# ArduTX_TX_Battery_Powered.net
KiCad netlist of a schematic drawn in EAGLE
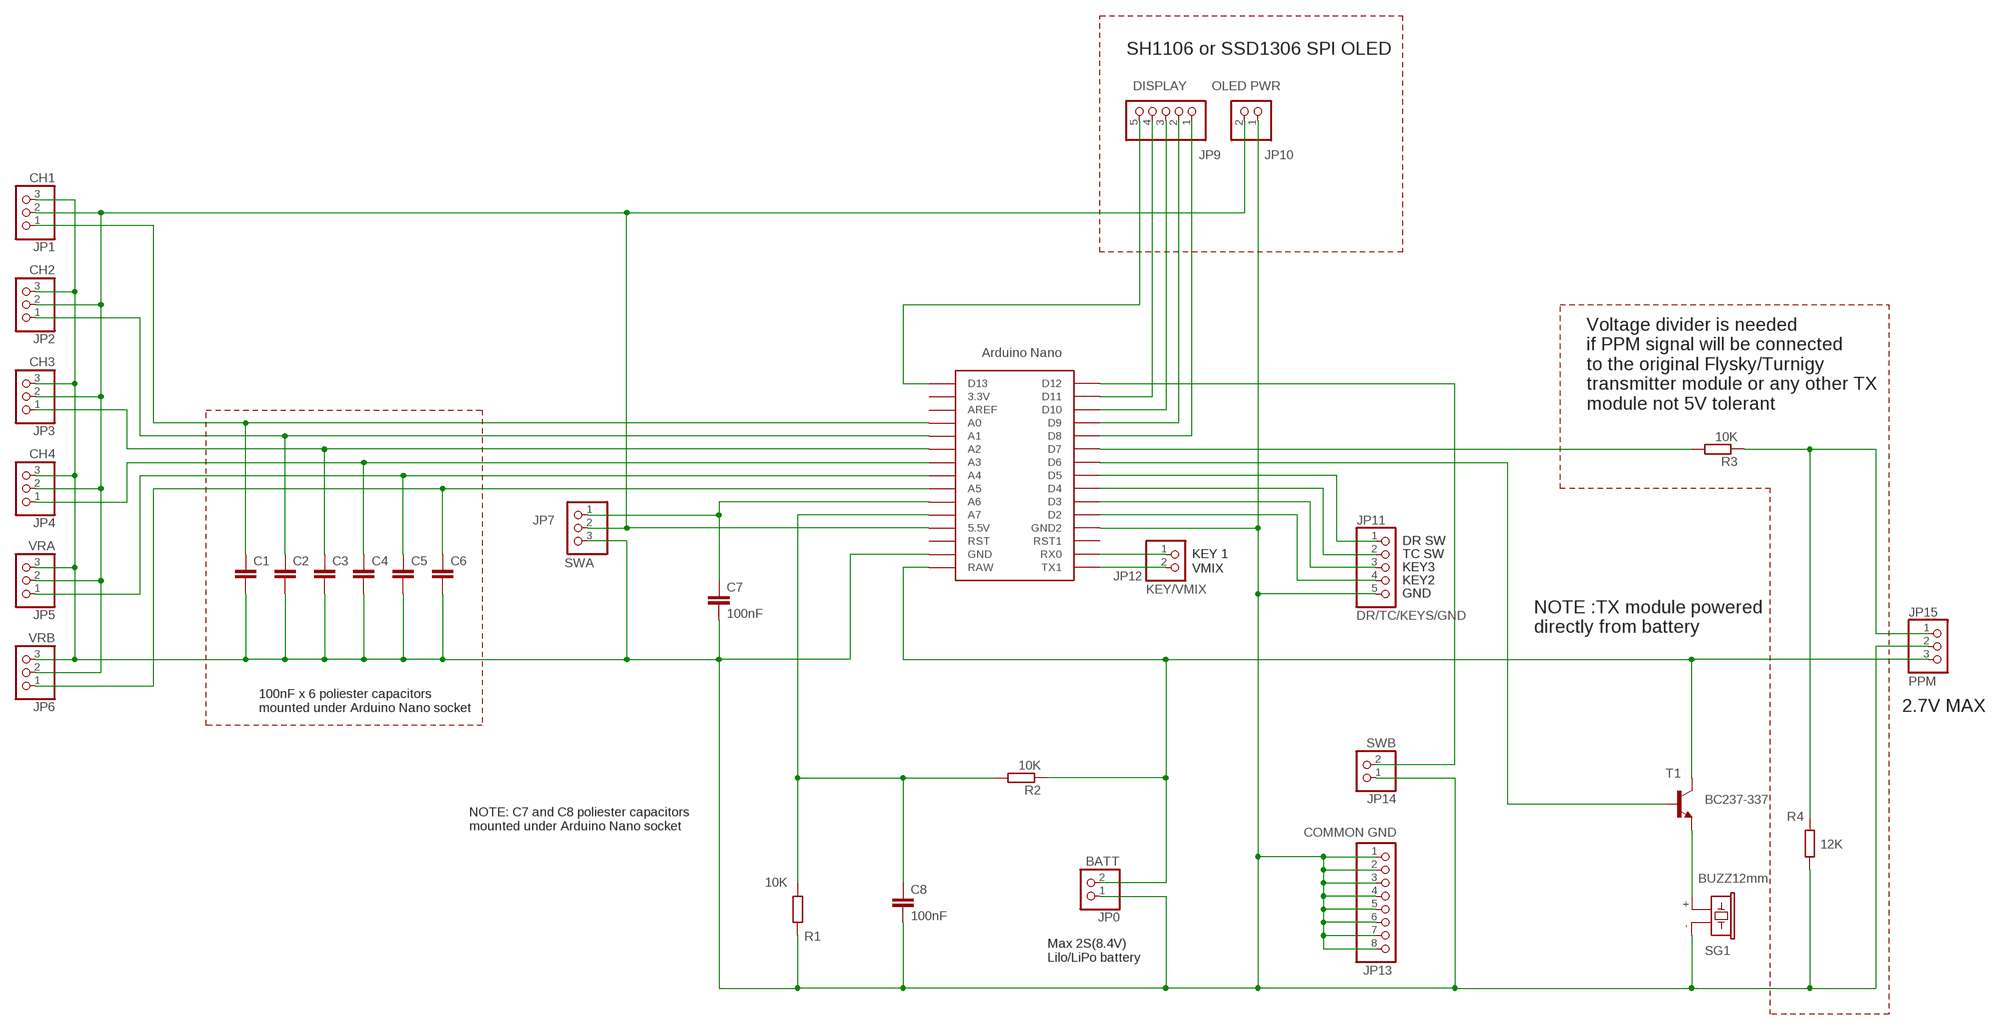
[diagram p0: schematic, sheet 1]

(export (version "E")
  (design (tool "Eeschema 10.0.6"))
  (components
    (comp (ref "ARDUINO-NANO")
      (value "NANO")
      (footprint "eagle-import:NANO")
      (libsource (lib "eagle-import") (part "NANO"))
    )
    (comp (ref "C1")
      (value "C-EU050-025X075")
      (footprint "eagle-import:C050-025X075")
      (libsource (lib "eagle-import") (part "C-EU050-025X075"))
    )
    (comp (ref "C2")
      (value "C-EU050-025X075")
      (footprint "eagle-import:C050-025X075")
      (libsource (lib "eagle-import") (part "C-EU050-025X075"))
    )
    (comp (ref "C3")
      (value "C-EU050-025X075")
      (footprint "eagle-import:C050-025X075")
      (libsource (lib "eagle-import") (part "C-EU050-025X075"))
    )
    (comp (ref "C4")
      (value "C-EU050-025X075")
      (footprint "eagle-import:C050-025X075")
      (libsource (lib "eagle-import") (part "C-EU050-025X075"))
    )
    (comp (ref "C5")
      (value "C-EU050-025X075")
      (footprint "eagle-import:C050-025X075")
      (libsource (lib "eagle-import") (part "C-EU050-025X075"))
    )
    (comp (ref "C6")
      (value "C-EU050-025X075")
      (footprint "eagle-import:C050-025X075")
      (libsource (lib "eagle-import") (part "C-EU050-025X075"))
    )
    (comp (ref "C7")
      (value "100nF")
      (footprint "eagle-import:C050-025X075")
      (libsource (lib "eagle-import") (part "C-EU050-025X075"))
    )
    (comp (ref "C8")
      (value "100nF")
      (footprint "eagle-import:C050-025X075")
      (libsource (lib "eagle-import") (part "C-EU050-025X075"))
    )
    (comp (ref "JP0")
      (value "BATT")
      (footprint "eagle-import:1X02")
      (libsource (lib "eagle-import") (part "PINHD-1X2"))
    )
    (comp (ref "JP1")
      (value "CH1")
      (footprint "eagle-import:1X03")
      (libsource (lib "eagle-import") (part "PINHD-1X3"))
    )
    (comp (ref "JP2")
      (value "CH2")
      (footprint "eagle-import:1X03")
      (libsource (lib "eagle-import") (part "PINHD-1X3"))
    )
    (comp (ref "JP3")
      (value "CH3")
      (footprint "eagle-import:1X03")
      (libsource (lib "eagle-import") (part "PINHD-1X3"))
    )
    (comp (ref "JP4")
      (value "CH4")
      (footprint "eagle-import:1X03")
      (libsource (lib "eagle-import") (part "PINHD-1X3"))
    )
    (comp (ref "JP5")
      (value "VRA")
      (footprint "eagle-import:1X03")
      (libsource (lib "eagle-import") (part "PINHD-1X3"))
    )
    (comp (ref "JP6")
      (value "VRB")
      (footprint "eagle-import:1X03")
      (libsource (lib "eagle-import") (part "PINHD-1X3"))
    )
    (comp (ref "JP7")
      (value "SWA")
      (footprint "eagle-import:1X03")
      (libsource (lib "eagle-import") (part "PINHD-1X3"))
    )
    (comp (ref "JP9")
      (value "DISPLAY")
      (footprint "eagle-import:1X05")
      (libsource (lib "eagle-import") (part "PINHD-1X5"))
    )
    (comp (ref "JP10")
      (value "OLED PWR")
      (footprint "eagle-import:1X02")
      (libsource (lib "eagle-import") (part "PINHD-1X2"))
    )
    (comp (ref "JP11")
      (value "DR/TC/KEYS/GND")
      (footprint "eagle-import:1X05")
      (libsource (lib "eagle-import") (part "PINHD-1X5"))
    )
    (comp (ref "JP12")
      (value "KEY/VMIX")
      (footprint "eagle-import:1X02")
      (libsource (lib "eagle-import") (part "PINHD-1X2"))
    )
    (comp (ref "JP13")
      (value "COMMON GND")
      (footprint "eagle-import:1X08")
      (libsource (lib "eagle-import") (part "PINHD-1X8"))
    )
    (comp (ref "JP14")
      (value "SWB")
      (footprint "eagle-import:1X02")
      (libsource (lib "eagle-import") (part "PINHD-1X2"))
    )
    (comp (ref "JP15")
      (value "PPM")
      (footprint "eagle-import:1X03")
      (libsource (lib "eagle-import") (part "PINHD-1X3"))
    )
    (comp (ref "R1")
      (value "10K")
      (footprint "eagle-import:0207_8")
      (libsource (lib "eagle-import") (part "R-EU_0207/8"))
    )
    (comp (ref "R2")
      (value "10K")
      (footprint "eagle-import:0207_8")
      (libsource (lib "eagle-import") (part "R-EU_0207/8"))
    )
    (comp (ref "R3")
      (value "10K")
      (footprint "eagle-import:0207_8")
      (libsource (lib "eagle-import") (part "R-EU_0207/8"))
    )
    (comp (ref "R4")
      (value "12K")
      (footprint "eagle-import:0207_8")
      (libsource (lib "eagle-import") (part "R-EU_0207/8"))
    )
    (comp (ref "SG1")
      (value "BUZZ12mm")
      (footprint "eagle-import:F_CM12P")
      (libsource (lib "eagle-import") (part "F/CM12P"))
    )
    (comp (ref "T1")
      (value "BC237-337")
      (footprint "eagle-import:TO92")
      (libsource (lib "eagle-import") (part "BC337"))
    )
  )
  (nets
    (net (code "1") (name "Net-(ARDUINO-NANO-5.5V)") (class "Default")
      (node (ref "ARDUINO-NANO") (pin "5V") (pinfunction "5.5V_5V") (pintype "bidirectional"))
      (node (ref "JP1") (pin "2") (pinfunction "2_2") (pintype "passive"))
      (node (ref "JP10") (pin "2") (pinfunction "2_2") (pintype "passive"))
      (node (ref "JP2") (pin "2") (pinfunction "2_2") (pintype "passive"))
      (node (ref "JP3") (pin "2") (pinfunction "2_2") (pintype "passive"))
      (node (ref "JP4") (pin "2") (pinfunction "2_2") (pintype "passive"))
      (node (ref "JP5") (pin "2") (pinfunction "2_2") (pintype "passive"))
      (node (ref "JP6") (pin "2") (pinfunction "2_2") (pintype "passive"))
      (node (ref "JP7") (pin "2") (pinfunction "2_2") (pintype "passive"))
    )
    (net (code "2") (name "Net-(ARDUINO-NANO-GND2)") (class "Default")
      (node (ref "ARDUINO-NANO") (pin "GND") (pinfunction "GND_GND") (pintype "bidirectional"))
      (node (ref "ARDUINO-NANO") (pin "GND1") (pinfunction "GND2_GND1") (pintype "bidirectional"))
      (node (ref "C1") (pin "2") (pinfunction "2_2") (pintype "passive"))
      (node (ref "C2") (pin "2") (pinfunction "2_2") (pintype "passive"))
      (node (ref "C3") (pin "2") (pinfunction "2_2") (pintype "passive"))
      (node (ref "C4") (pin "2") (pinfunction "2_2") (pintype "passive"))
      (node (ref "C5") (pin "2") (pinfunction "2_2") (pintype "passive"))
      (node (ref "C6") (pin "2") (pinfunction "2_2") (pintype "passive"))
      (node (ref "C7") (pin "2") (pinfunction "2_2") (pintype "passive"))
      (node (ref "C8") (pin "2") (pinfunction "2_2") (pintype "passive"))
      (node (ref "JP0") (pin "1") (pinfunction "1_1") (pintype "passive"))
      (node (ref "JP1") (pin "3") (pinfunction "3_3") (pintype "passive"))
      (node (ref "JP10") (pin "1") (pinfunction "1_1") (pintype "passive"))
      (node (ref "JP11") (pin "5") (pinfunction "5_5") (pintype "passive"))
      (node (ref "JP13") (pin "1") (pinfunction "1_1") (pintype "passive"))
      (node (ref "JP13") (pin "2") (pinfunction "2_2") (pintype "passive"))
      (node (ref "JP13") (pin "3") (pinfunction "3_3") (pintype "passive"))
      (node (ref "JP13") (pin "4") (pinfunction "4_4") (pintype "passive"))
      (node (ref "JP13") (pin "5") (pinfunction "5_5") (pintype "passive"))
      (node (ref "JP13") (pin "6") (pinfunction "6_6") (pintype "passive"))
      (node (ref "JP13") (pin "7") (pinfunction "7_7") (pintype "passive"))
      (node (ref "JP13") (pin "8") (pinfunction "8_8") (pintype "passive"))
      (node (ref "JP14") (pin "1") (pinfunction "1_1") (pintype "passive"))
      (node (ref "JP15") (pin "2") (pinfunction "2_2") (pintype "passive"))
      (node (ref "JP2") (pin "3") (pinfunction "3_3") (pintype "passive"))
      (node (ref "JP3") (pin "3") (pinfunction "3_3") (pintype "passive"))
      (node (ref "JP4") (pin "3") (pinfunction "3_3") (pintype "passive"))
      (node (ref "JP5") (pin "3") (pinfunction "3_3") (pintype "passive"))
      (node (ref "JP6") (pin "3") (pinfunction "3_3") (pintype "passive"))
      (node (ref "JP7") (pin "3") (pinfunction "3_3") (pintype "passive"))
      (node (ref "R1") (pin "2") (pinfunction "2_2") (pintype "passive"))
      (node (ref "R4") (pin "1") (pinfunction "1_1") (pintype "passive"))
      (node (ref "SG1") (pin "-") (pinfunction "2_-") (pintype "passive"))
    )
    (net (code "3") (name "Net-(ARDUINO-NANO-PadA0)") (class "Default")
      (node (ref "ARDUINO-NANO") (pin "A0") (pinfunction "A0_A0") (pintype "bidirectional"))
      (node (ref "C1") (pin "1") (pinfunction "1_1") (pintype "passive"))
      (node (ref "JP1") (pin "1") (pinfunction "1_1") (pintype "passive"))
    )
    (net (code "4") (name "Net-(ARDUINO-NANO-PadA1)") (class "Default")
      (node (ref "ARDUINO-NANO") (pin "A1") (pinfunction "A1_A1") (pintype "bidirectional"))
      (node (ref "C2") (pin "1") (pinfunction "1_1") (pintype "passive"))
      (node (ref "JP2") (pin "1") (pinfunction "1_1") (pintype "passive"))
    )
    (net (code "5") (name "Net-(ARDUINO-NANO-PadA2)") (class "Default")
      (node (ref "ARDUINO-NANO") (pin "A2") (pinfunction "A2_A2") (pintype "bidirectional"))
      (node (ref "C3") (pin "1") (pinfunction "1_1") (pintype "passive"))
      (node (ref "JP3") (pin "1") (pinfunction "1_1") (pintype "passive"))
    )
    (net (code "6") (name "Net-(ARDUINO-NANO-PadA3)") (class "Default")
      (node (ref "ARDUINO-NANO") (pin "A3") (pinfunction "A3_A3") (pintype "bidirectional"))
      (node (ref "C4") (pin "1") (pinfunction "1_1") (pintype "passive"))
      (node (ref "JP4") (pin "1") (pinfunction "1_1") (pintype "passive"))
    )
    (net (code "7") (name "Net-(ARDUINO-NANO-PadA4)") (class "Default")
      (node (ref "ARDUINO-NANO") (pin "A4") (pinfunction "A4_A4") (pintype "bidirectional"))
      (node (ref "C5") (pin "1") (pinfunction "1_1") (pintype "passive"))
      (node (ref "JP5") (pin "1") (pinfunction "1_1") (pintype "passive"))
    )
    (net (code "8") (name "Net-(ARDUINO-NANO-PadA5)") (class "Default")
      (node (ref "ARDUINO-NANO") (pin "A5") (pinfunction "A5_A5") (pintype "bidirectional"))
      (node (ref "C6") (pin "1") (pinfunction "1_1") (pintype "passive"))
      (node (ref "JP6") (pin "1") (pinfunction "1_1") (pintype "passive"))
    )
    (net (code "9") (name "Net-(ARDUINO-NANO-PadA6)") (class "Default")
      (node (ref "ARDUINO-NANO") (pin "A6") (pinfunction "A6_A6") (pintype "bidirectional"))
      (node (ref "C7") (pin "1") (pinfunction "1_1") (pintype "passive"))
      (node (ref "JP7") (pin "1") (pinfunction "1_1") (pintype "passive"))
    )
    (net (code "10") (name "Net-(ARDUINO-NANO-PadA7)") (class "Default")
      (node (ref "ARDUINO-NANO") (pin "A7") (pinfunction "A7_A7") (pintype "bidirectional"))
      (node (ref "C8") (pin "1") (pinfunction "1_1") (pintype "passive"))
      (node (ref "R1") (pin "1") (pinfunction "1_1") (pintype "passive"))
      (node (ref "R2") (pin "2") (pinfunction "2_2") (pintype "passive"))
    )
    (net (code "11") (name "Net-(ARDUINO-NANO-PadD2)") (class "Default")
      (node (ref "ARDUINO-NANO") (pin "D2") (pinfunction "D2_D2") (pintype "bidirectional"))
      (node (ref "JP11") (pin "4") (pinfunction "4_4") (pintype "passive"))
    )
    (net (code "12") (name "Net-(ARDUINO-NANO-PadD3)") (class "Default")
      (node (ref "ARDUINO-NANO") (pin "D3") (pinfunction "D3_D3") (pintype "bidirectional"))
      (node (ref "JP11") (pin "3") (pinfunction "3_3") (pintype "passive"))
    )
    (net (code "13") (name "Net-(ARDUINO-NANO-PadD4)") (class "Default")
      (node (ref "ARDUINO-NANO") (pin "D4") (pinfunction "D4_D4") (pintype "bidirectional"))
      (node (ref "JP11") (pin "2") (pinfunction "2_2") (pintype "passive"))
    )
    (net (code "14") (name "Net-(ARDUINO-NANO-PadD5)") (class "Default")
      (node (ref "ARDUINO-NANO") (pin "D5") (pinfunction "D5_D5") (pintype "bidirectional"))
      (node (ref "JP11") (pin "1") (pinfunction "1_1") (pintype "passive"))
    )
    (net (code "15") (name "Net-(ARDUINO-NANO-PadD7)") (class "Default")
      (node (ref "ARDUINO-NANO") (pin "D7") (pinfunction "D7_D7") (pintype "bidirectional"))
      (node (ref "R3") (pin "2") (pinfunction "2_2") (pintype "passive"))
    )
    (net (code "16") (name "Net-(ARDUINO-NANO-PadD8)") (class "Default")
      (node (ref "ARDUINO-NANO") (pin "D8") (pinfunction "D8_D8") (pintype "bidirectional"))
      (node (ref "JP9") (pin "1") (pinfunction "1_1") (pintype "passive"))
    )
    (net (code "17") (name "Net-(ARDUINO-NANO-PadD9)") (class "Default")
      (node (ref "ARDUINO-NANO") (pin "D9") (pinfunction "D9_D9") (pintype "bidirectional"))
      (node (ref "JP9") (pin "2") (pinfunction "2_2") (pintype "passive"))
    )
    (net (code "18") (name "Net-(ARDUINO-NANO-PadD10)") (class "Default")
      (node (ref "ARDUINO-NANO") (pin "D10") (pinfunction "D10_D10") (pintype "bidirectional"))
      (node (ref "JP9") (pin "3") (pinfunction "3_3") (pintype "passive"))
    )
    (net (code "19") (name "Net-(ARDUINO-NANO-PadD11)") (class "Default")
      (node (ref "ARDUINO-NANO") (pin "D11") (pinfunction "D11_D11") (pintype "bidirectional"))
      (node (ref "JP9") (pin "4") (pinfunction "4_4") (pintype "passive"))
    )
    (net (code "20") (name "Net-(ARDUINO-NANO-PadD12)") (class "Default")
      (node (ref "ARDUINO-NANO") (pin "D12") (pinfunction "D12_D12") (pintype "bidirectional"))
      (node (ref "JP14") (pin "2") (pinfunction "2_2") (pintype "passive"))
    )
    (net (code "21") (name "Net-(ARDUINO-NANO-PadD13)") (class "Default")
      (node (ref "ARDUINO-NANO") (pin "D13") (pinfunction "D13_D13") (pintype "bidirectional"))
      (node (ref "JP9") (pin "5") (pinfunction "5_5") (pintype "passive"))
    )
    (net (code "22") (name "Net-(ARDUINO-NANO-RX0)") (class "Default")
      (node (ref "ARDUINO-NANO") (pin "RX1") (pinfunction "RX0_RX1") (pintype "bidirectional"))
      (node (ref "JP12") (pin "1") (pinfunction "1_1") (pintype "passive"))
    )
    (net (code "23") (name "Net-(ARDUINO-NANO-TX1)") (class "Default")
      (node (ref "ARDUINO-NANO") (pin "TX0") (pinfunction "TX1_TX0") (pintype "bidirectional"))
      (node (ref "JP12") (pin "2") (pinfunction "2_2") (pintype "passive"))
    )
    (net (code "24") (name "Net-(JP15-Pad1)") (class "Default")
      (node (ref "JP15") (pin "1") (pinfunction "1_1") (pintype "passive"))
      (node (ref "R3") (pin "1") (pinfunction "1_1") (pintype "passive"))
      (node (ref "R4") (pin "2") (pinfunction "2_2") (pintype "passive"))
    )
    (net (code "25") (name "Net-(SG1-1)") (class "Default")
      (node (ref "SG1") (pin "+") (pinfunction "1_+") (pintype "passive"))
      (node (ref "T1") (pin "1") (pinfunction "E_1") (pintype "passive"))
    )
    (net (code "26") (name "Net-(T1-B)") (class "Default")
      (node (ref "ARDUINO-NANO") (pin "D6") (pinfunction "D6_D6") (pintype "bidirectional"))
      (node (ref "T1") (pin "2") (pinfunction "B_2") (pintype "passive"))
    )
    (net (code "27") (name "Net-(T1-C)") (class "Default")
      (node (ref "ARDUINO-NANO") (pin "RAW") (pinfunction "RAW_RAW") (pintype "bidirectional"))
      (node (ref "JP0") (pin "2") (pinfunction "2_2") (pintype "passive"))
      (node (ref "JP15") (pin "3") (pinfunction "3_3") (pintype "passive"))
      (node (ref "R2") (pin "1") (pinfunction "1_1") (pintype "passive"))
      (node (ref "T1") (pin "3") (pinfunction "C_3") (pintype "passive"))
    )
    (net (code "28") (name "unconnected-(ARDUINO-NANO-Pad3.3V)") (class "Default")
      (node (ref "ARDUINO-NANO") (pin "3.3V") (pinfunction "3.3V_3.3V") (pintype "bidirectional"))
    )
    (net (code "29") (name "unconnected-(ARDUINO-NANO-PadAREF)") (class "Default")
      (node (ref "ARDUINO-NANO") (pin "AREF") (pinfunction "AREF_AREF") (pintype "bidirectional"))
    )
    (net (code "30") (name "unconnected-(ARDUINO-NANO-PadRST)") (class "Default")
      (node (ref "ARDUINO-NANO") (pin "RST") (pinfunction "RST_RST") (pintype "bidirectional"))
    )
    (net (code "31") (name "unconnected-(ARDUINO-NANO-PadRST1)") (class "Default")
      (node (ref "ARDUINO-NANO") (pin "RST1") (pinfunction "RST1_RST1") (pintype "bidirectional"))
    )
  )
)
